# Sheet2.net
KiCad netlist of a schematic drawn in Altium Designer
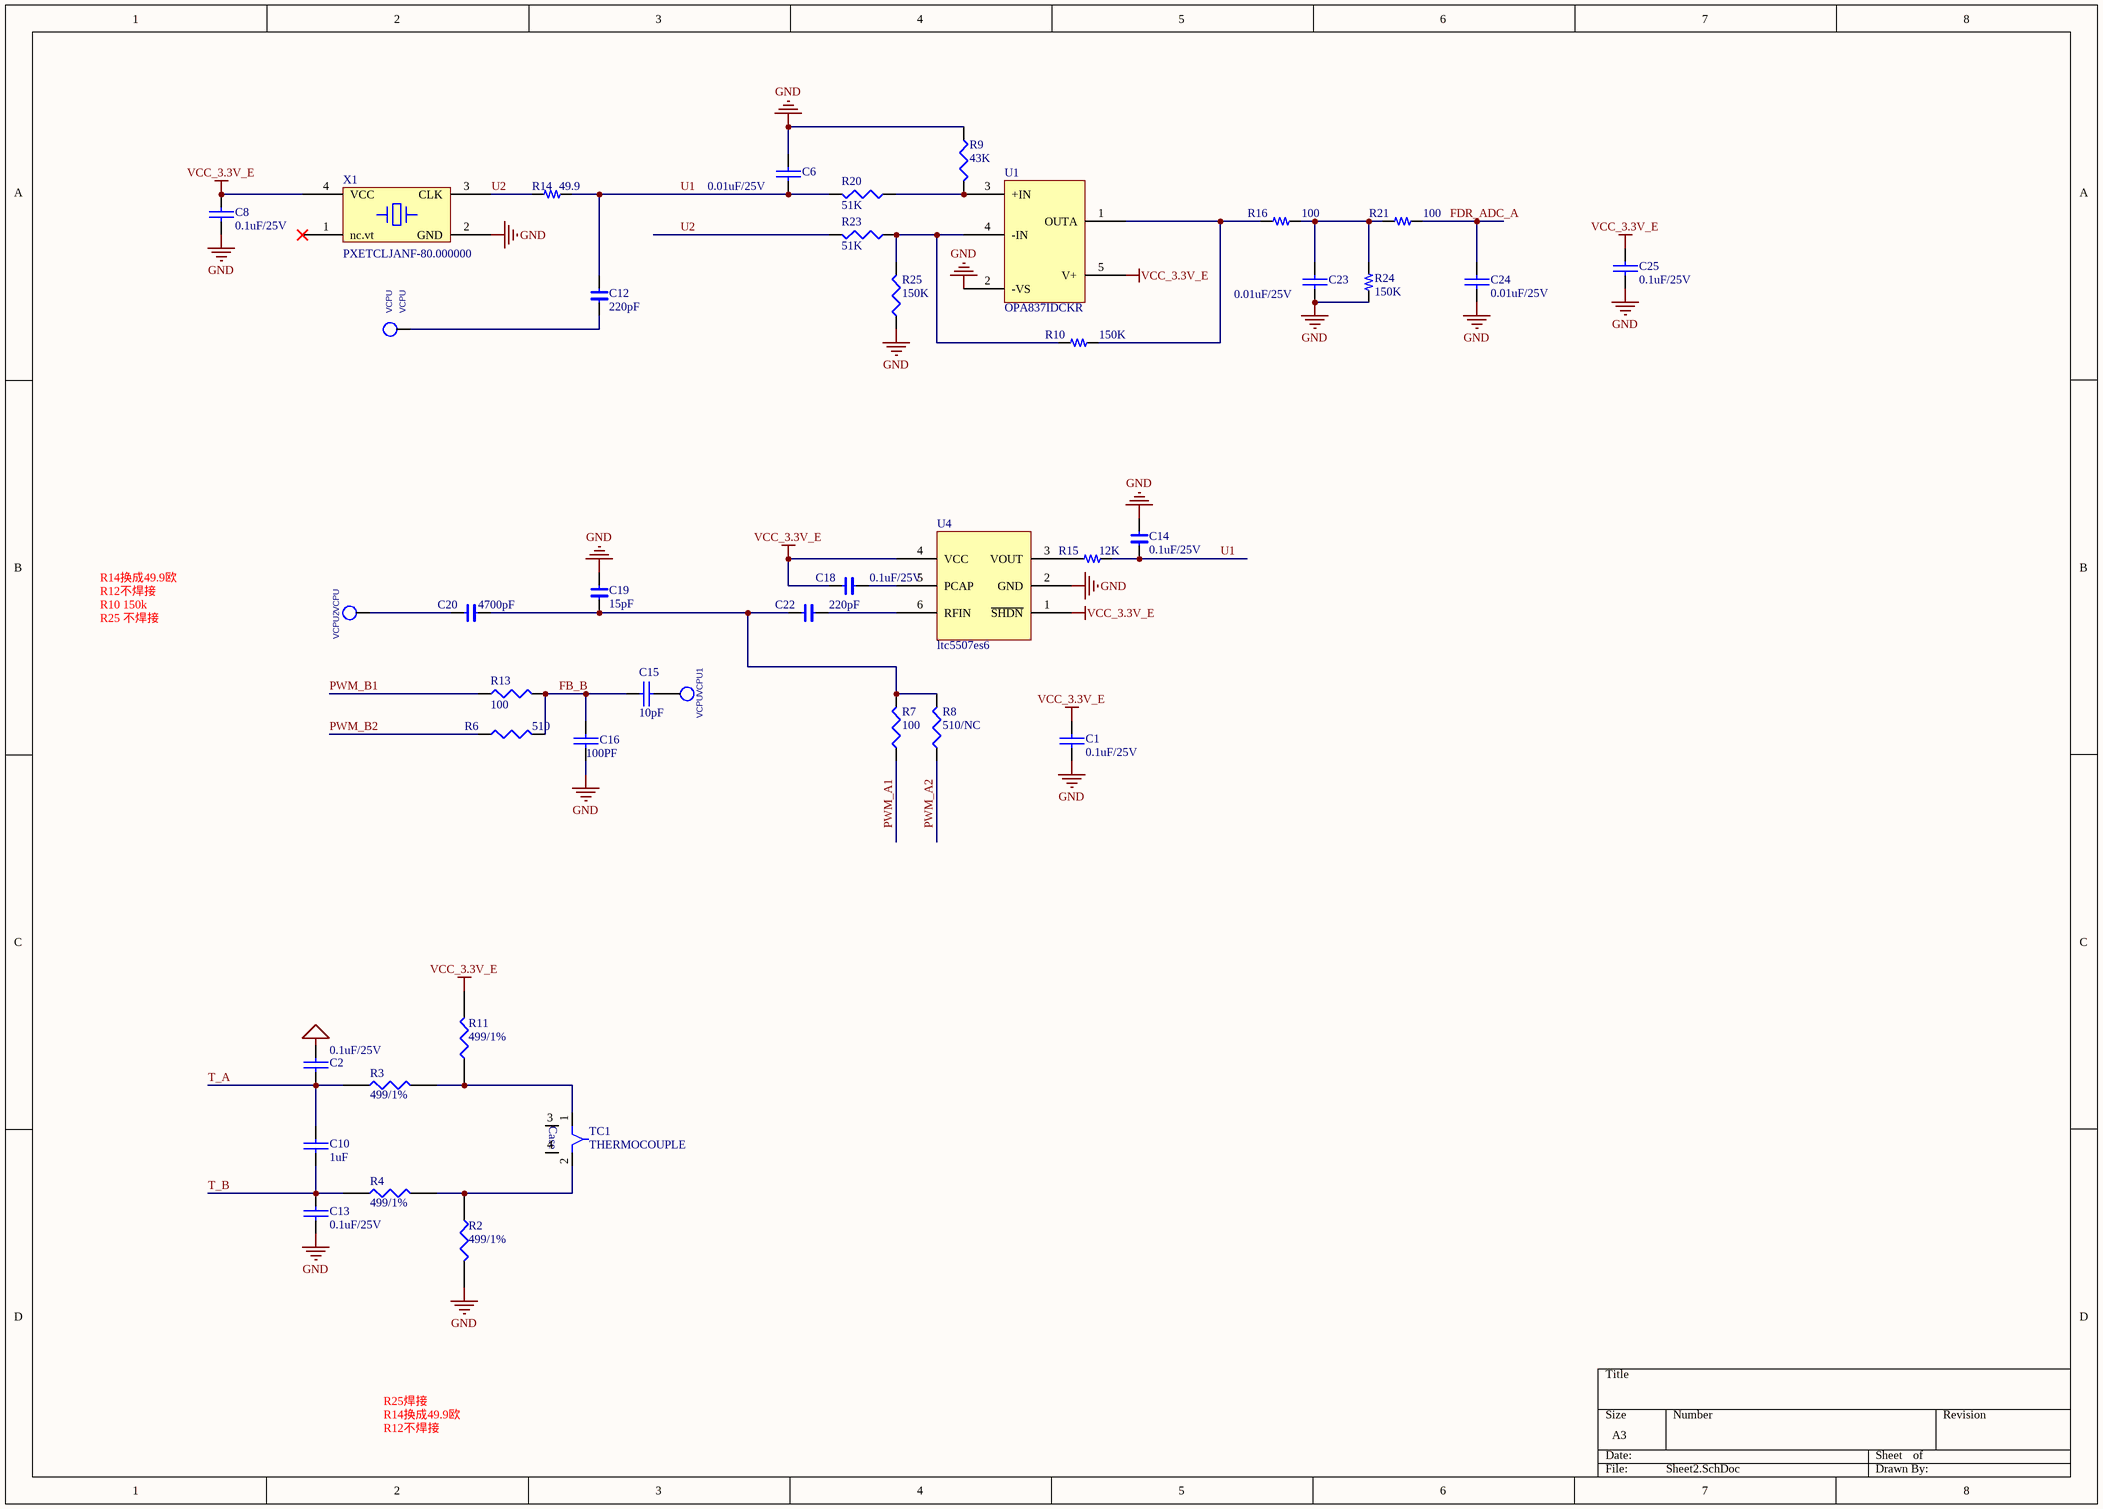
[diagram p0: Sheet2.SchDoc]

(export (version "E")
  (design (tool "Eeschema 10.0.6"))
  (components
    (comp (ref "C1")
      (value "0.1uF/25V")
      (footprint "0603C")
      (description "Capacitor")
      (libsource (lib "SM") (part "CAP"))
    )
    (comp (ref "C2")
      (value "0.1uF/25V")
      (footprint "0603c")
      (description "Capacitor")
      (libsource (lib "*") (part "CAP"))
    )
    (comp (ref "C6")
      (value "0.01uF/25V")
      (footprint "0603C")
      (description "Capacitor")
      (libsource (lib "SM") (part "CAP"))
    )
    (comp (ref "C8")
      (value "0.1uF/25V")
      (footprint "0603C")
      (description "Capacitor")
      (libsource (lib "SM") (part "CAP"))
    )
    (comp (ref "C10")
      (value "1uF")
      (footprint "0603c")
      (description "Capacitor")
      (libsource (lib "*") (part "CAP"))
    )
    (comp (ref "C12")
      (value "220pF")
      (footprint "0603C")
      (description "C")
      (libsource (lib "YxmSCH") (part "C"))
    )
    (comp (ref "C13")
      (value "0.1uF/25V")
      (footprint "0603c")
      (description "Capacitor")
      (libsource (lib "*") (part "CAP"))
    )
    (comp (ref "C14")
      (value "0.1uF/25V")
      (footprint "0603C")
      (description "C")
      (libsource (lib "YxmSCH") (part "C"))
    )
    (comp (ref "C15")
      (value "10pF")
      (footprint "0603C")
      (description "Capacitor")
      (libsource (lib "SM") (part "CAP"))
    )
    (comp (ref "C16")
      (value "100PF")
      (footprint "0603C")
      (description "Capacitor")
      (libsource (lib "SM") (part "CAP"))
    )
    (comp (ref "C18")
      (value "0.1uF/25V")
      (footprint "0603C")
      (description "C")
      (libsource (lib "YxmSCH") (part "C"))
    )
    (comp (ref "C19")
      (value "15pF")
      (footprint "0603C")
      (description "C")
      (libsource (lib "YxmSCH") (part "C"))
    )
    (comp (ref "C20")
      (value "4700pF")
      (footprint "0603C")
      (description "C")
      (libsource (lib "YxmSCH") (part "C"))
    )
    (comp (ref "C22")
      (value "220pF")
      (footprint "0603C")
      (description "C")
      (libsource (lib "YxmSCH") (part "C"))
    )
    (comp (ref "C23")
      (value "0.01uF/25V")
      (footprint "0603C")
      (description "Capacitor")
      (libsource (lib "SM") (part "CAP"))
    )
    (comp (ref "C24")
      (value "0.01uF/25V")
      (footprint "0603C")
      (description "Capacitor")
      (libsource (lib "SM") (part "CAP"))
    )
    (comp (ref "C25")
      (value "0.1uF/25V")
      (footprint "0603C")
      (description "Capacitor")
      (libsource (lib "SM") (part "CAP"))
    )
    (comp (ref "R2") (value "499/1%") (footprint "0603r") (libsource (lib "*") (part "RES1")))
    (comp (ref "R3") (value "499/1%") (footprint "0603r") (libsource (lib "*") (part "RES1")))
    (comp (ref "R4") (value "499/1%") (footprint "0603r") (libsource (lib "*") (part "RES1")))
    (comp (ref "R6")
      (value "510")
      (footprint "0603R")
      (description "Resistor")
      (fields (field (name "PUBLISHER") "Altium Limited"))
      (libsource (lib "SM") (part "Res3"))
    )
    (comp (ref "R7")
      (value "100")
      (footprint "0603R")
      (description "Resistor")
      (fields (field (name "PUBLISHER") "Altium Limited"))
      (libsource (lib "SM") (part "Res3"))
    )
    (comp (ref "R8")
      (value "510/NC")
      (footprint "0603R")
      (description "Resistor")
      (fields (field (name "PUBLISHER") "Altium Limited"))
      (libsource (lib "SM") (part "Res3"))
    )
    (comp (ref "R9")
      (value "43K")
      (footprint "0603R")
      (description "Resistor")
      (fields (field (name "PUBLISHER") "Altium Limited"))
      (libsource (lib "SM") (part "Res3"))
    )
    (comp (ref "R10")
      (value "150K")
      (footprint "0603R")
      (description "R")
      (libsource (lib "JRJ_1") (part "R"))
    )
    (comp (ref "R11") (value "499/1%") (footprint "0603r") (libsource (lib "*") (part "RES1")))
    (comp (ref "R13")
      (value "100")
      (footprint "0603R")
      (description "Resistor")
      (fields (field (name "PUBLISHER") "Altium Limited"))
      (libsource (lib "SM") (part "Res3"))
    )
    (comp (ref "R14") (value "49.9") (footprint "0603r") (description "R") (libsource (lib "JRJ") (part "R")))
    (comp (ref "R15") (value "12K") (footprint "0603r") (description "R") (libsource (lib "JRJ") (part "R")))
    (comp (ref "R16")
      (value "100")
      (footprint "0603R")
      (description "R")
      (libsource (lib "JRJ_1") (part "R"))
    )
    (comp (ref "R20")
      (value "51K")
      (footprint "0603R")
      (description "Resistor")
      (fields (field (name "PUBLISHER") "Altium Limited"))
      (libsource (lib "SM") (part "Res3"))
    )
    (comp (ref "R21")
      (value "100")
      (footprint "0603R")
      (description "R")
      (libsource (lib "JRJ_1") (part "R"))
    )
    (comp (ref "R23")
      (value "51K")
      (footprint "0603R")
      (description "Resistor")
      (fields (field (name "PUBLISHER") "Altium Limited"))
      (libsource (lib "SM") (part "Res3"))
    )
    (comp (ref "R24")
      (value "150K")
      (footprint "0603R")
      (description "R")
      (libsource (lib "JRJ_1") (part "R"))
    )
    (comp (ref "R25")
      (value "150K")
      (footprint "0603R")
      (description "Resistor")
      (fields (field (name "PUBLISHER") "Altium Limited"))
      (libsource (lib "SM") (part "Res3"))
    )
    (comp (ref "TC1") (value "THERMOCOUPLE") (footprint "0603R") (libsource (lib "*") (part "THERMOCOUPLE")))
    (comp (ref "U1")
      (value "OPA837IDCKR")
      (footprint "SC70-5")
      (libsource (lib "Schlib_20110825") (part "OPA837 DCK"))
    )
    (comp (ref "U4") (value "ltc5507es6") (footprint "SOT23-6") (libsource (lib "stm32") (part "ltc5507es6")))
    (comp (ref "VCPU") (value "VCPU") (footprint "probe") (libsource (lib "*") (part "T_POINT_R")))
    (comp (ref "VCPU1") (value "VCPU") (footprint "probe") (libsource (lib "*") (part "T_POINT_R")))
    (comp (ref "VCPU2") (value "VCPU") (footprint "probe") (libsource (lib "*") (part "T_POINT_R")))
    (comp (ref "X1")
      (value "PXETCLJANF-80.000000")
      (footprint "XTAL4TN_7050")
      (libsource (lib "Y0801_V13") (part "XTAL4S"))
    )
  )
  (nets
    (net (code "1") (name "/FB_B") (class "Default")
      (node (ref "C15") (pin "1") (pinfunction "1_1") (pintype "passive"))
      (node (ref "C16") (pin "1") (pinfunction "1_1") (pintype "passive"))
      (node (ref "R13") (pin "2") (pinfunction "2_2") (pintype "passive"))
      (node (ref "R6") (pin "2") (pinfunction "2_2") (pintype "passive"))
    )
    (net (code "2") (name "/FDR_ADC_A") (class "Default")
      (node (ref "C24") (pin "2") (pinfunction "2_2") (pintype "passive"))
      (node (ref "R21") (pin "2") (pintype "passive"))
    )
    (net (code "3") (name "/PWM_A1") (class "Default")
      (node (ref "R7") (pin "1") (pinfunction "1_1") (pintype "passive"))
    )
    (net (code "4") (name "/PWM_A2") (class "Default")
      (node (ref "R8") (pin "1") (pinfunction "1_1") (pintype "passive"))
    )
    (net (code "5") (name "/PWM_B1") (class "Default")
      (node (ref "R13") (pin "1") (pinfunction "1_1") (pintype "passive"))
    )
    (net (code "6") (name "/PWM_B2") (class "Default")
      (node (ref "R6") (pin "1") (pinfunction "1_1") (pintype "passive"))
    )
    (net (code "7") (name "/T_A") (class "Default")
      (node (ref "C10") (pin "1") (pinfunction "1_1") (pintype "passive"))
      (node (ref "C2") (pin "1") (pinfunction "1_1") (pintype "passive"))
      (node (ref "R3") (pin "1") (pinfunction "1_1") (pintype "passive"))
    )
    (net (code "8") (name "/T_B") (class "Default")
      (node (ref "C10") (pin "2") (pinfunction "2_2") (pintype "passive"))
      (node (ref "C13") (pin "1") (pinfunction "1_1") (pintype "passive"))
      (node (ref "R4") (pin "1") (pinfunction "1_1") (pintype "passive"))
    )
    (net (code "9") (name "/U1") (class "Default")
      (node (ref "C12") (pin "2") (pintype "passive"))
      (node (ref "C14") (pin "1") (pintype "passive"))
      (node (ref "C6") (pin "1") (pinfunction "1_1") (pintype "passive"))
      (node (ref "R14") (pin "2") (pintype "passive"))
      (node (ref "R15") (pin "1") (pintype "passive"))
      (node (ref "R20") (pin "2") (pinfunction "2_2") (pintype "passive"))
    )
    (net (code "10") (name "/U2") (class "Default")
      (node (ref "R14") (pin "1") (pintype "passive"))
      (node (ref "R23") (pin "2") (pinfunction "2_2") (pintype "passive"))
      (node (ref "X1") (pin "3") (pinfunction "CLK_3") (pintype "passive"))
    )
    (net (code "11") (name "GND") (class "Default")
      (node (ref "C1") (pin "1") (pinfunction "1_1") (pintype "passive"))
      (node (ref "C13") (pin "2") (pinfunction "2_2") (pintype "passive"))
      (node (ref "C14") (pin "2") (pintype "passive"))
      (node (ref "C16") (pin "2") (pinfunction "2_2") (pintype "passive"))
      (node (ref "C19") (pin "2") (pintype "passive"))
      (node (ref "C2") (pin "2") (pinfunction "2_2") (pintype "passive"))
      (node (ref "C23") (pin "1") (pinfunction "1_1") (pintype "passive"))
      (node (ref "C24") (pin "1") (pinfunction "1_1") (pintype "passive"))
      (node (ref "C25") (pin "1") (pinfunction "1_1") (pintype "passive"))
      (node (ref "C6") (pin "2") (pinfunction "2_2") (pintype "passive"))
      (node (ref "C8") (pin "2") (pinfunction "2_2") (pintype "passive"))
      (node (ref "R2") (pin "2") (pinfunction "2_2") (pintype "passive"))
      (node (ref "R24") (pin "1") (pintype "passive"))
      (node (ref "R25") (pin "1") (pinfunction "1_1") (pintype "passive"))
      (node (ref "R9") (pin "1") (pinfunction "1_1") (pintype "passive"))
      (node (ref "U1") (pin "2") (pinfunction "-VS_2") (pintype "passive"))
      (node (ref "U4") (pin "2") (pinfunction "GND_2") (pintype "passive"))
      (node (ref "X1") (pin "2") (pinfunction "GND_2") (pintype "power_in"))
    )
    (net (code "12") (name "Net-(C19-Pad1)") (class "Default")
      (node (ref "C19") (pin "1") (pintype "passive"))
      (node (ref "C20") (pin "2") (pintype "passive"))
      (node (ref "C22") (pin "1") (pintype "passive"))
      (node (ref "R7") (pin "2") (pinfunction "2_2") (pintype "passive"))
      (node (ref "R8") (pin "2") (pinfunction "2_2") (pintype "passive"))
    )
    (net (code "13") (name "Net-(C23-Pad2)") (class "Default")
      (node (ref "C23") (pin "2") (pinfunction "2_2") (pintype "passive"))
      (node (ref "R16") (pin "2") (pintype "passive"))
      (node (ref "R21") (pin "1") (pintype "passive"))
      (node (ref "R24") (pin "2") (pintype "passive"))
    )
    (net (code "14") (name "Net-(R2-Pad1)") (class "Default")
      (node (ref "R2") (pin "1") (pinfunction "1_1") (pintype "passive"))
      (node (ref "R4") (pin "2") (pinfunction "2_2") (pintype "passive"))
      (node (ref "TC1") (pin "2") (pinfunction "2_2") (pintype "passive"))
    )
    (net (code "15") (name "Net-(R11-Pad1)") (class "Default")
      (node (ref "R11") (pin "1") (pinfunction "1_1") (pintype "passive"))
      (node (ref "R3") (pin "2") (pinfunction "2_2") (pintype "passive"))
      (node (ref "TC1") (pin "1") (pinfunction "1_1") (pintype "passive"))
    )
    (net (code "16") (name "Net-(U1-+IN)") (class "Default")
      (node (ref "R20") (pin "1") (pinfunction "1_1") (pintype "passive"))
      (node (ref "R9") (pin "2") (pinfunction "2_2") (pintype "passive"))
      (node (ref "U1") (pin "3") (pinfunction "+IN_3") (pintype "passive"))
    )
    (net (code "17") (name "Net-(U1--IN)") (class "Default")
      (node (ref "R10") (pin "1") (pintype "passive"))
      (node (ref "R23") (pin "1") (pinfunction "1_1") (pintype "passive"))
      (node (ref "R25") (pin "2") (pinfunction "2_2") (pintype "passive"))
      (node (ref "U1") (pin "4") (pinfunction "-IN_4") (pintype "passive"))
    )
    (net (code "18") (name "Net-(U1-OUTA)") (class "Default")
      (node (ref "R10") (pin "2") (pintype "passive"))
      (node (ref "R16") (pin "1") (pintype "passive"))
      (node (ref "U1") (pin "1") (pinfunction "OUTA_1") (pintype "passive"))
    )
    (net (code "19") (name "Net-(U4-PCAP)") (class "Default")
      (node (ref "C18") (pin "2") (pintype "passive"))
      (node (ref "U4") (pin "5") (pinfunction "PCAP_5") (pintype "passive"))
    )
    (net (code "20") (name "Net-(U4-RFIN)") (class "Default")
      (node (ref "C22") (pin "2") (pintype "passive"))
      (node (ref "U4") (pin "6") (pinfunction "RFIN_6") (pintype "passive"))
    )
    (net (code "21") (name "Net-(U4-VOUT)") (class "Default")
      (node (ref "R15") (pin "2") (pintype "passive"))
      (node (ref "U4") (pin "3") (pinfunction "VOUT_3") (pintype "passive"))
    )
    (net (code "22") (name "Net-(VCPU-TP)") (class "Default")
      (node (ref "C12") (pin "1") (pintype "passive"))
      (node (ref "VCPU") (pin "1") (pinfunction "TP_1") (pintype "passive"))
    )
    (net (code "23") (name "Net-(VCPU1-TP)") (class "Default")
      (node (ref "C15") (pin "2") (pinfunction "2_2") (pintype "passive"))
      (node (ref "VCPU1") (pin "1") (pinfunction "TP_1") (pintype "passive"))
    )
    (net (code "24") (name "Net-(VCPU2-TP)") (class "Default")
      (node (ref "C20") (pin "1") (pintype "passive"))
      (node (ref "VCPU2") (pin "1") (pinfunction "TP_1") (pintype "passive"))
    )
    (net (code "25") (name "VCC_3.3V_E") (class "Default")
      (node (ref "C1") (pin "2") (pinfunction "2_2") (pintype "passive"))
      (node (ref "C18") (pin "1") (pintype "passive"))
      (node (ref "C25") (pin "2") (pinfunction "2_2") (pintype "passive"))
      (node (ref "C8") (pin "1") (pinfunction "1_1") (pintype "passive"))
      (node (ref "R11") (pin "2") (pinfunction "2_2") (pintype "passive"))
      (node (ref "U1") (pin "5") (pinfunction "V+_5") (pintype "passive"))
      (node (ref "U4") (pin "1") (pinfunction "~{SHDN}_1") (pintype "passive"))
      (node (ref "U4") (pin "4") (pinfunction "VCC_4") (pintype "passive"))
      (node (ref "X1") (pin "4") (pinfunction "VCC_4") (pintype "power_in"))
    )
    (net (code "26") (name "unconnected-(TC1-Pad3)") (class "Default")
      (node (ref "TC1") (pin "3") (pinfunction "3_3") (pintype "passive"))
    )
    (net (code "27") (name "unconnected-(TC1-Pad4)") (class "Default")
      (node (ref "TC1") (pin "4") (pinfunction "4_4") (pintype "passive"))
    )
    (net (code "28") (name "unconnected-(X1-nc.vt-Pad1)") (class "Default")
      (node (ref "X1") (pin "1") (pinfunction "nc.vt_1") (pintype "passive+no_connect"))
    )
  )
)
